# ISOLATED_PSU.net
KiCad netlist of a schematic drawn in Altium Designer
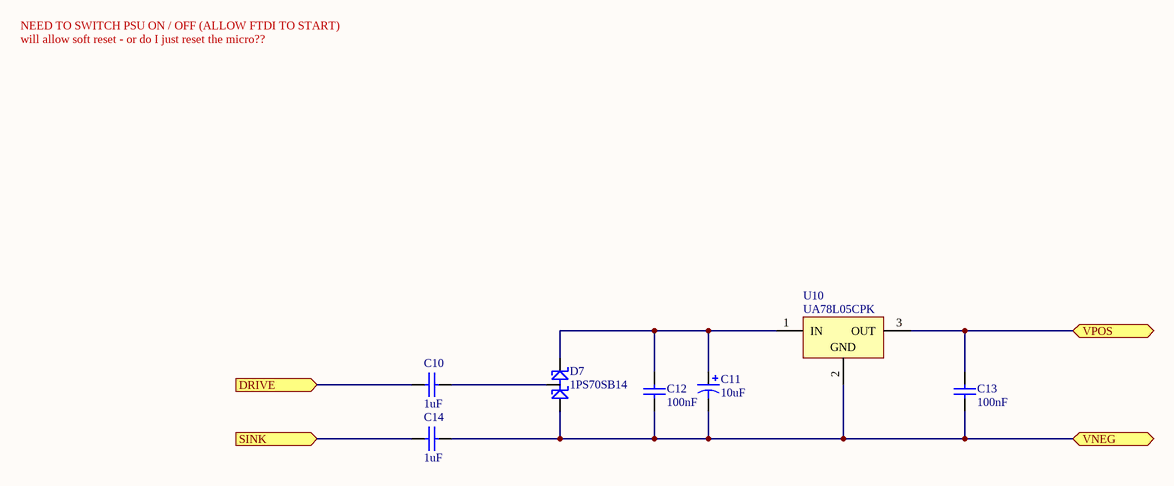
[diagram p0: ISOLATED PSU.SchDoc]

(export (version "E")
  (design (tool "Eeschema 10.0.6"))
  (components
    (comp (ref "C10")
      (value "1uF")
      (footprint "RES (3D) - 1210")
      (description "CAPACITOR SMD 0603")
      (fields (field (name "MOUSER PART NO.") "77-VJ1206V105MXATBC") (field (name "MANUFACTURER") "Vishay"))
      (libsource (lib "Mi-Call Schematic") (part "CAP"))
    )
    (comp (ref "C11")
      (value "10uF")
      (footprint "CAP ELECTRO SIZE-B")
      (description "Polarized Capacitor (Radial)")
      (libsource (lib "Miscellaneous Devices") (part "Cap Pol1"))
    )
    (comp (ref "C12")
      (value "100nF")
      (footprint "CAP (3D) - 0603")
      (description "Capacitor")
      (libsource (lib "Miscellaneous Devices") (part "Cap"))
    )
    (comp (ref "C13")
      (value "100nF")
      (footprint "CAP (3D) - 0603")
      (description "Capacitor")
      (libsource (lib "Miscellaneous Devices") (part "Cap"))
    )
    (comp (ref "C14")
      (value "1uF")
      (footprint "RES (3D) - 1210")
      (description "CAPACITOR SMD 0603")
      (fields (field (name "MOUSER PART NO.") "77-VJ1206V105MXATBC") (field (name "MANUFACTURER") "Vishay"))
      (libsource (lib "Mi-Call Schematic") (part "CAP"))
    )
    (comp (ref "D7")
      (value "1PS70SB14")
      (footprint "SOT23-3L")
      (description "DUAL DIODE, SCHOTTKY")
      (fields
        (field (name "MOUSER PART NO.") "771-1PS70SB14115")
        (field (name "MANUFACTURER") "NXP SEMICONDUCTORS")
      )
      (libsource (lib "NASCO") (part "1PS70SB14"))
    )
    (comp (ref "U10")
      (value "UA78L05CPK")
      (footprint "SOT89")
      (description "3-Terminal Positive Fixed Voltage Regulator")
      (fields
        (field (name "MOUSER PART NO.") "595-UA78L05CPK")
        (field (name "MANUFACTURER") "Texas Instruments")
      )
      (libsource (lib "NASCO") (part "UA78L05CPK"))
    )
  )
  (nets
    (net (code "1") (name "/DRIVE") (class "Default")
      (node (ref "C10") (pin "1") (pinfunction "1_1") (pintype "passive"))
    )
    (net (code "2") (name "/SINK") (class "Default")
      (node (ref "C14") (pin "1") (pinfunction "1_1") (pintype "passive"))
    )
    (net (code "3") (name "/VNEG") (class "Default")
      (node (ref "C11") (pin "2") (pinfunction "2_2") (pintype "passive"))
      (node (ref "C12") (pin "1") (pinfunction "1_1") (pintype "passive"))
      (node (ref "C13") (pin "1") (pinfunction "1_1") (pintype "passive"))
      (node (ref "C14") (pin "2") (pinfunction "2_2") (pintype "passive"))
      (node (ref "D7") (pin "1") (pinfunction "A1_1") (pintype "passive"))
      (node (ref "U10") (pin "2") (pinfunction "GND_2") (pintype "power_in"))
    )
    (net (code "4") (name "/VPOS") (class "Default")
      (node (ref "C13") (pin "2") (pinfunction "2_2") (pintype "passive"))
      (node (ref "U10") (pin "3") (pinfunction "OUT_3") (pintype "power_in"))
    )
    (net (code "5") (name "Net-(D7-C1{slash}A2)") (class "Default")
      (node (ref "C10") (pin "2") (pinfunction "2_2") (pintype "passive"))
      (node (ref "D7") (pin "3") (pinfunction "C1/A2_3") (pintype "passive"))
    )
    (net (code "6") (name "Net-(D7-C2)") (class "Default")
      (node (ref "C11") (pin "1") (pinfunction "1_1") (pintype "passive"))
      (node (ref "C12") (pin "2") (pinfunction "2_2") (pintype "passive"))
      (node (ref "D7") (pin "2") (pinfunction "C2_2") (pintype "passive"))
      (node (ref "U10") (pin "1") (pinfunction "IN_1") (pintype "power_in"))
    )
  )
)
